# K40_panel_V1.net
KiCad netlist of a schematic drawn in EAGLE
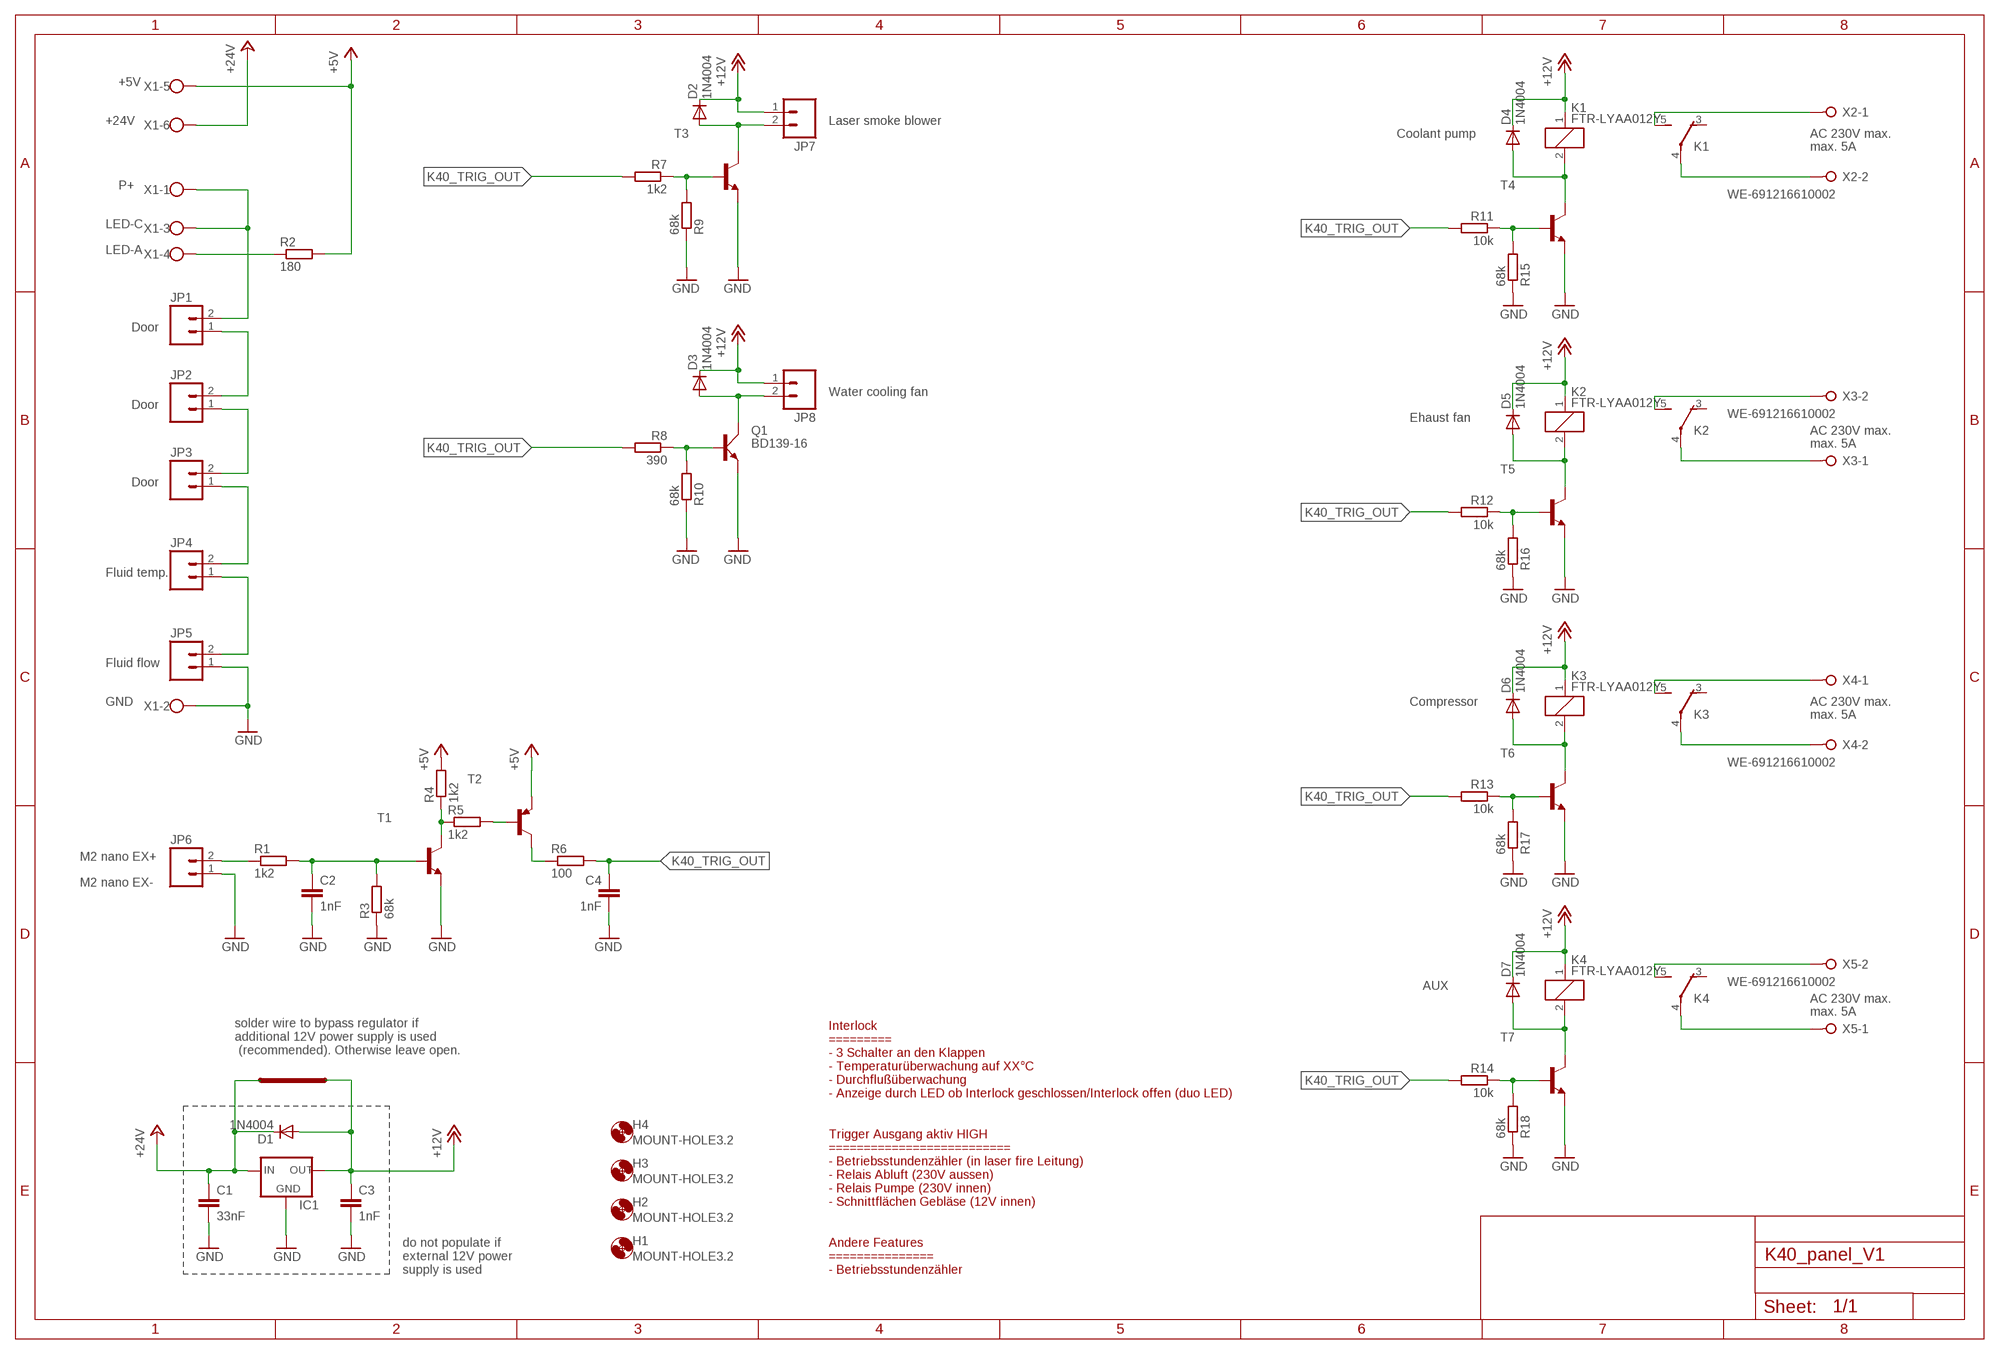
[diagram p0: schematic, sheet 1]

(export (version "E")
  (design (tool "Eeschema 10.0.6"))
  (components
    (comp (ref "C1")
      (value "33nF")
      (footprint "eagle-import:C050-024X044")
      (libsource (lib "eagle-import") (part "C-EU050-024X044"))
    )
    (comp (ref "C2")
      (value "1nF")
      (footprint "eagle-import:C050-024X044")
      (libsource (lib "eagle-import") (part "C-EU050-024X044"))
    )
    (comp (ref "C3")
      (value "1nF")
      (footprint "eagle-import:C050-024X044")
      (libsource (lib "eagle-import") (part "C-EU050-024X044"))
    )
    (comp (ref "C4")
      (value "1nF")
      (footprint "eagle-import:C050-024X044")
      (libsource (lib "eagle-import") (part "C-EU050-024X044"))
    )
    (comp (ref "D1")
      (value "1N4004")
      (footprint "eagle-import:DO41-10")
      (libsource (lib "eagle-import") (part "1N4004"))
    )
    (comp (ref "D2")
      (value "1N4004")
      (footprint "eagle-import:DO41-10")
      (libsource (lib "eagle-import") (part "1N4004"))
    )
    (comp (ref "D3")
      (value "1N4004")
      (footprint "eagle-import:DO41-10")
      (libsource (lib "eagle-import") (part "1N4004"))
    )
    (comp (ref "D4")
      (value "1N4004")
      (footprint "eagle-import:DO41-10")
      (libsource (lib "eagle-import") (part "1N4004"))
    )
    (comp (ref "D5")
      (value "1N4004")
      (footprint "eagle-import:DO41-10")
      (libsource (lib "eagle-import") (part "1N4004"))
    )
    (comp (ref "D6")
      (value "1N4004")
      (footprint "eagle-import:DO41-10")
      (libsource (lib "eagle-import") (part "1N4004"))
    )
    (comp (ref "D7")
      (value "1N4004")
      (footprint "eagle-import:DO41-10")
      (libsource (lib "eagle-import") (part "1N4004"))
    )
    (comp (ref "H1")
      (value "MOUNT-HOLE3.2")
      (footprint "eagle-import:3,2")
      (libsource (lib "eagle-import") (part "MOUNT-HOLE3.2"))
    )
    (comp (ref "H2")
      (value "MOUNT-HOLE3.2")
      (footprint "eagle-import:3,2")
      (libsource (lib "eagle-import") (part "MOUNT-HOLE3.2"))
    )
    (comp (ref "H3")
      (value "MOUNT-HOLE3.2")
      (footprint "eagle-import:3,2")
      (libsource (lib "eagle-import") (part "MOUNT-HOLE3.2"))
    )
    (comp (ref "H4")
      (value "MOUNT-HOLE3.2")
      (footprint "eagle-import:3,2")
      (libsource (lib "eagle-import") (part "MOUNT-HOLE3.2"))
    )
    (comp (ref "IC1")
      (value "78XXS")
      (footprint "eagle-import:78XXS")
      (libsource (lib "eagle-import") (part "78XXS"))
    )
    (comp (ref "JP1")
      (value "M02POLAR")
      (footprint "eagle-import:MOLEX-1X2")
      (libsource (lib "eagle-import") (part "M02POLAR"))
    )
    (comp (ref "JP2")
      (value "M02POLAR")
      (footprint "eagle-import:MOLEX-1X2")
      (libsource (lib "eagle-import") (part "M02POLAR"))
    )
    (comp (ref "JP3")
      (value "M02POLAR")
      (footprint "eagle-import:MOLEX-1X2")
      (libsource (lib "eagle-import") (part "M02POLAR"))
    )
    (comp (ref "JP4")
      (value "M02POLAR")
      (footprint "eagle-import:MOLEX-1X2")
      (libsource (lib "eagle-import") (part "M02POLAR"))
    )
    (comp (ref "JP5")
      (value "M02POLAR")
      (footprint "eagle-import:MOLEX-1X2")
      (libsource (lib "eagle-import") (part "M02POLAR"))
    )
    (comp (ref "JP6")
      (value "M02POLAR")
      (footprint "eagle-import:MOLEX-1X2")
      (libsource (lib "eagle-import") (part "M02POLAR"))
    )
    (comp (ref "JP7")
      (value "M02POLAR")
      (footprint "eagle-import:MOLEX-1X2")
      (libsource (lib "eagle-import") (part "M02POLAR"))
    )
    (comp (ref "JP8")
      (value "M02POLAR")
      (footprint "eagle-import:MOLEX-1X2")
      (libsource (lib "eagle-import") (part "M02POLAR"))
    )
    (comp (ref "K1")
      (value "FTR-LYAA012Y")
      (footprint "eagle-import:FTR-LYC")
      (libsource (lib "eagle-import") (part "FTR-LYC12"))
    )
    (comp (ref "K2")
      (value "FTR-LYAA012Y")
      (footprint "eagle-import:FTR-LYC")
      (libsource (lib "eagle-import") (part "FTR-LYC12"))
    )
    (comp (ref "K3")
      (value "FTR-LYAA012Y")
      (footprint "eagle-import:FTR-LYC")
      (libsource (lib "eagle-import") (part "FTR-LYC12"))
    )
    (comp (ref "K4")
      (value "FTR-LYAA012Y")
      (footprint "eagle-import:FTR-LYC")
      (libsource (lib "eagle-import") (part "FTR-LYC12"))
    )
    (comp (ref "Q1")
      (value "BD139-16")
      (footprint "eagle-import:TO126AV")
      (libsource (lib "eagle-import") (part "BD139"))
    )
    (comp (ref "R1")
      (value "1k2")
      (footprint "eagle-import:0204_7")
      (libsource (lib "eagle-import") (part "R-EU_0204/7"))
    )
    (comp (ref "R2")
      (value "180")
      (footprint "eagle-import:0204_7")
      (libsource (lib "eagle-import") (part "R-EU_0204/7"))
    )
    (comp (ref "R3")
      (value "68k")
      (footprint "eagle-import:0204_7")
      (libsource (lib "eagle-import") (part "R-EU_0204/7"))
    )
    (comp (ref "R4")
      (value "1k2")
      (footprint "eagle-import:0204_7")
      (libsource (lib "eagle-import") (part "R-EU_0204/7"))
    )
    (comp (ref "R5")
      (value "1k2")
      (footprint "eagle-import:0204_7")
      (libsource (lib "eagle-import") (part "R-EU_0204/7"))
    )
    (comp (ref "R6")
      (value "100")
      (footprint "eagle-import:0204_7")
      (libsource (lib "eagle-import") (part "R-EU_0204/7"))
    )
    (comp (ref "R7")
      (value "1k2")
      (footprint "eagle-import:0204_7")
      (libsource (lib "eagle-import") (part "R-EU_0204/7"))
    )
    (comp (ref "R8")
      (value "390")
      (footprint "eagle-import:0204_7")
      (libsource (lib "eagle-import") (part "R-EU_0204/7"))
    )
    (comp (ref "R9")
      (value "68k")
      (footprint "eagle-import:0204_7")
      (libsource (lib "eagle-import") (part "R-EU_0204/7"))
    )
    (comp (ref "R10")
      (value "68k")
      (footprint "eagle-import:0204_7")
      (libsource (lib "eagle-import") (part "R-EU_0204/7"))
    )
    (comp (ref "R11")
      (value "10k")
      (footprint "eagle-import:0204_7")
      (libsource (lib "eagle-import") (part "R-EU_0204/7"))
    )
    (comp (ref "R12")
      (value "10k")
      (footprint "eagle-import:0204_7")
      (libsource (lib "eagle-import") (part "R-EU_0204/7"))
    )
    (comp (ref "R13")
      (value "10k")
      (footprint "eagle-import:0204_7")
      (libsource (lib "eagle-import") (part "R-EU_0204/7"))
    )
    (comp (ref "R14")
      (value "10k")
      (footprint "eagle-import:0204_7")
      (libsource (lib "eagle-import") (part "R-EU_0204/7"))
    )
    (comp (ref "R15")
      (value "68k")
      (footprint "eagle-import:0204_7")
      (libsource (lib "eagle-import") (part "R-EU_0204/7"))
    )
    (comp (ref "R16")
      (value "68k")
      (footprint "eagle-import:0204_7")
      (libsource (lib "eagle-import") (part "R-EU_0204/7"))
    )
    (comp (ref "R17")
      (value "68k")
      (footprint "eagle-import:0204_7")
      (libsource (lib "eagle-import") (part "R-EU_0204/7"))
    )
    (comp (ref "R18")
      (value "68k")
      (footprint "eagle-import:0204_7")
      (libsource (lib "eagle-import") (part "R-EU_0204/7"))
    )
    (comp (ref "T1")
      (value "2N4401-NPN-TO92-EBC")
      (footprint "eagle-import:TO92-EBC")
      (libsource (lib "eagle-import") (part "-NPN-TO92-EBC2N4401"))
    )
    (comp (ref "T2")
      (value "2N4403-PNP-TO92-EBC")
      (footprint "eagle-import:TO92-EBC")
      (libsource (lib "eagle-import") (part "-PNP-TO92-EBC2N4403"))
    )
    (comp (ref "T3")
      (value "2N4401-NPN-TO92-EBC")
      (footprint "eagle-import:TO92-EBC")
      (libsource (lib "eagle-import") (part "-NPN-TO92-EBC2N4401"))
    )
    (comp (ref "T4")
      (value "2N4401-NPN-TO92-EBC")
      (footprint "eagle-import:TO92-EBC")
      (libsource (lib "eagle-import") (part "-NPN-TO92-EBC2N4401"))
    )
    (comp (ref "T5")
      (value "2N4401-NPN-TO92-EBC")
      (footprint "eagle-import:TO92-EBC")
      (libsource (lib "eagle-import") (part "-NPN-TO92-EBC2N4401"))
    )
    (comp (ref "T6")
      (value "2N4401-NPN-TO92-EBC")
      (footprint "eagle-import:TO92-EBC")
      (libsource (lib "eagle-import") (part "-NPN-TO92-EBC2N4401"))
    )
    (comp (ref "T7")
      (value "2N4401-NPN-TO92-EBC")
      (footprint "eagle-import:TO92-EBC")
      (libsource (lib "eagle-import") (part "-NPN-TO92-EBC2N4401"))
    )
    (comp (ref "X1")
      (value "W237-6")
      (footprint "eagle-import:W237-6")
      (libsource (lib "eagle-import") (part "W237-6"))
    )
    (comp (ref "X2")
      (value "WE-691216610002")
      (footprint "eagle-import:W237-2N")
      (libsource (lib "eagle-import") (part "W237-2N"))
    )
    (comp (ref "X3")
      (value "WE-691216610002")
      (footprint "eagle-import:W237-2N")
      (libsource (lib "eagle-import") (part "W237-2N"))
    )
    (comp (ref "X4")
      (value "WE-691216610002")
      (footprint "eagle-import:W237-2N")
      (libsource (lib "eagle-import") (part "W237-2N"))
    )
    (comp (ref "X5")
      (value "WE-691216610002")
      (footprint "eagle-import:W237-2N")
      (libsource (lib "eagle-import") (part "W237-2N"))
    )
  )
  (nets
    (net (code "1") (name "+5V") (class "Default")
      (node (ref "R2") (pin "2") (pinfunction "2_2") (pintype "passive"))
      (node (ref "R4") (pin "2") (pinfunction "2_2") (pintype "passive"))
      (node (ref "T2") (pin "E") (pinfunction "E_E") (pintype "passive"))
      (node (ref "X1") (pin "5") (pinfunction "KL_5") (pintype "passive"))
    )
    (net (code "2") (name "+12V") (class "Default")
      (node (ref "C3") (pin "1") (pinfunction "1_1") (pintype "passive"))
      (node (ref "D1") (pin "A") (pinfunction "A_A") (pintype "passive"))
      (node (ref "D2") (pin "C") (pinfunction "C_C") (pintype "passive"))
      (node (ref "D3") (pin "C") (pinfunction "C_C") (pintype "passive"))
      (node (ref "D4") (pin "C") (pinfunction "C_C") (pintype "passive"))
      (node (ref "D5") (pin "C") (pinfunction "C_C") (pintype "passive"))
      (node (ref "D6") (pin "C") (pinfunction "C_C") (pintype "passive"))
      (node (ref "D7") (pin "C") (pinfunction "C_C") (pintype "passive"))
      (node (ref "IC1") (pin "OUT") (pinfunction "OUT_OUT") (pintype "passive"))
      (node (ref "JP7") (pin "1") (pinfunction "1_1") (pintype "passive"))
      (node (ref "JP8") (pin "1") (pinfunction "1_1") (pintype "passive"))
      (node (ref "K1") (pin "1") (pinfunction "1_1") (pintype "passive"))
      (node (ref "K2") (pin "1") (pinfunction "1_1") (pintype "passive"))
      (node (ref "K3") (pin "1") (pinfunction "1_1") (pintype "passive"))
      (node (ref "K4") (pin "1") (pinfunction "1_1") (pintype "passive"))
    )
    (net (code "3") (name "+24V") (class "Default")
      (node (ref "C1") (pin "1") (pinfunction "1_1") (pintype "passive"))
      (node (ref "D1") (pin "C") (pinfunction "C_C") (pintype "passive"))
      (node (ref "IC1") (pin "IN") (pinfunction "IN_IN") (pintype "input"))
      (node (ref "X1") (pin "6") (pinfunction "KL_6") (pintype "passive"))
    )
    (net (code "4") (name "GND") (class "Default")
      (node (ref "C1") (pin "2") (pinfunction "2_2") (pintype "passive"))
      (node (ref "C2") (pin "2") (pinfunction "2_2") (pintype "passive"))
      (node (ref "C3") (pin "2") (pinfunction "2_2") (pintype "passive"))
      (node (ref "C4") (pin "2") (pinfunction "2_2") (pintype "passive"))
      (node (ref "IC1") (pin "GND") (pinfunction "GND_GND") (pintype "input"))
      (node (ref "JP5") (pin "1") (pinfunction "1_1") (pintype "passive"))
      (node (ref "JP6") (pin "1") (pinfunction "1_1") (pintype "passive"))
      (node (ref "Q1") (pin "E") (pinfunction "E_E") (pintype "passive"))
      (node (ref "R10") (pin "1") (pinfunction "1_1") (pintype "passive"))
      (node (ref "R15") (pin "1") (pinfunction "1_1") (pintype "passive"))
      (node (ref "R16") (pin "1") (pinfunction "1_1") (pintype "passive"))
      (node (ref "R17") (pin "1") (pinfunction "1_1") (pintype "passive"))
      (node (ref "R18") (pin "1") (pinfunction "1_1") (pintype "passive"))
      (node (ref "R3") (pin "1") (pinfunction "1_1") (pintype "passive"))
      (node (ref "R9") (pin "1") (pinfunction "1_1") (pintype "passive"))
      (node (ref "T1") (pin "E") (pinfunction "E_E") (pintype "passive"))
      (node (ref "T3") (pin "E") (pinfunction "E_E") (pintype "passive"))
      (node (ref "T4") (pin "E") (pinfunction "E_E") (pintype "passive"))
      (node (ref "T5") (pin "E") (pinfunction "E_E") (pintype "passive"))
      (node (ref "T6") (pin "E") (pinfunction "E_E") (pintype "passive"))
      (node (ref "T7") (pin "E") (pinfunction "E_E") (pintype "passive"))
      (node (ref "X1") (pin "2") (pinfunction "KL_2") (pintype "passive"))
    )
    (net (code "5") (name "K40_TRIG_OUT") (class "Default")
      (node (ref "C4") (pin "1") (pinfunction "1_1") (pintype "passive"))
      (node (ref "R11") (pin "2") (pinfunction "2_2") (pintype "passive"))
      (node (ref "R12") (pin "2") (pinfunction "2_2") (pintype "passive"))
      (node (ref "R13") (pin "2") (pinfunction "2_2") (pintype "passive"))
      (node (ref "R14") (pin "2") (pinfunction "2_2") (pintype "passive"))
      (node (ref "R6") (pin "2") (pinfunction "2_2") (pintype "passive"))
      (node (ref "R7") (pin "2") (pinfunction "2_2") (pintype "passive"))
      (node (ref "R8") (pin "2") (pinfunction "2_2") (pintype "passive"))
    )
    (net (code "6") (name "Net-(C2-Pad1)") (class "Default")
      (node (ref "C2") (pin "1") (pinfunction "1_1") (pintype "passive"))
      (node (ref "R1") (pin "2") (pinfunction "2_2") (pintype "passive"))
      (node (ref "R3") (pin "2") (pinfunction "2_2") (pintype "passive"))
      (node (ref "T1") (pin "B") (pinfunction "B_B") (pintype "passive"))
    )
    (net (code "7") (name "Net-(D2-PadA)") (class "Default")
      (node (ref "D2") (pin "A") (pinfunction "A_A") (pintype "passive"))
      (node (ref "JP7") (pin "2") (pinfunction "2_2") (pintype "passive"))
      (node (ref "T3") (pin "C") (pinfunction "C_C") (pintype "passive"))
    )
    (net (code "8") (name "Net-(D3-PadA)") (class "Default")
      (node (ref "D3") (pin "A") (pinfunction "A_A") (pintype "passive"))
      (node (ref "JP8") (pin "2") (pinfunction "2_2") (pintype "passive"))
      (node (ref "Q1") (pin "C") (pinfunction "C_C") (pintype "passive"))
    )
    (net (code "9") (name "Net-(D4-PadA)") (class "Default")
      (node (ref "D4") (pin "A") (pinfunction "A_A") (pintype "passive"))
      (node (ref "K1") (pin "2") (pinfunction "2_2") (pintype "passive"))
      (node (ref "T4") (pin "C") (pinfunction "C_C") (pintype "passive"))
    )
    (net (code "10") (name "Net-(D5-PadA)") (class "Default")
      (node (ref "D5") (pin "A") (pinfunction "A_A") (pintype "passive"))
      (node (ref "K2") (pin "2") (pinfunction "2_2") (pintype "passive"))
      (node (ref "T5") (pin "C") (pinfunction "C_C") (pintype "passive"))
    )
    (net (code "11") (name "Net-(D6-PadA)") (class "Default")
      (node (ref "D6") (pin "A") (pinfunction "A_A") (pintype "passive"))
      (node (ref "K3") (pin "2") (pinfunction "2_2") (pintype "passive"))
      (node (ref "T6") (pin "C") (pinfunction "C_C") (pintype "passive"))
    )
    (net (code "12") (name "Net-(D7-PadA)") (class "Default")
      (node (ref "D7") (pin "A") (pinfunction "A_A") (pintype "passive"))
      (node (ref "K4") (pin "2") (pinfunction "2_2") (pintype "passive"))
      (node (ref "T7") (pin "C") (pinfunction "C_C") (pintype "passive"))
    )
    (net (code "13") (name "Net-(JP1-Pad1)") (class "Default")
      (node (ref "JP1") (pin "1") (pinfunction "1_1") (pintype "passive"))
      (node (ref "JP2") (pin "2") (pinfunction "2_2") (pintype "passive"))
    )
    (net (code "14") (name "Net-(JP2-Pad1)") (class "Default")
      (node (ref "JP2") (pin "1") (pinfunction "1_1") (pintype "passive"))
      (node (ref "JP3") (pin "2") (pinfunction "2_2") (pintype "passive"))
    )
    (net (code "15") (name "Net-(JP3-Pad1)") (class "Default")
      (node (ref "JP3") (pin "1") (pinfunction "1_1") (pintype "passive"))
      (node (ref "JP4") (pin "2") (pinfunction "2_2") (pintype "passive"))
    )
    (net (code "16") (name "Net-(JP4-Pad1)") (class "Default")
      (node (ref "JP4") (pin "1") (pinfunction "1_1") (pintype "passive"))
      (node (ref "JP5") (pin "2") (pinfunction "2_2") (pintype "passive"))
    )
    (net (code "17") (name "Net-(JP6-Pad2)") (class "Default")
      (node (ref "JP6") (pin "2") (pinfunction "2_2") (pintype "passive"))
      (node (ref "R1") (pin "1") (pinfunction "1_1") (pintype "passive"))
    )
    (net (code "18") (name "Net-(K1A-P)") (class "Default")
      (node (ref "K1") (pin "4") (pinfunction "P_4") (pintype "passive"))
      (node (ref "X2") (pin "2") (pinfunction "KL_2") (pintype "passive"))
    )
    (net (code "19") (name "Net-(K1A-S)") (class "Default")
      (node (ref "K1") (pin "5") (pinfunction "S_5") (pintype "passive"))
      (node (ref "X2") (pin "1") (pinfunction "KL_1") (pintype "passive"))
    )
    (net (code "20") (name "Net-(K2A-P)") (class "Default")
      (node (ref "K2") (pin "4") (pinfunction "P_4") (pintype "passive"))
      (node (ref "X3") (pin "1") (pinfunction "KL_1") (pintype "passive"))
    )
    (net (code "21") (name "Net-(K2A-S)") (class "Default")
      (node (ref "K2") (pin "5") (pinfunction "S_5") (pintype "passive"))
      (node (ref "X3") (pin "2") (pinfunction "KL_2") (pintype "passive"))
    )
    (net (code "22") (name "Net-(K3A-P)") (class "Default")
      (node (ref "K3") (pin "4") (pinfunction "P_4") (pintype "passive"))
      (node (ref "X4") (pin "2") (pinfunction "KL_2") (pintype "passive"))
    )
    (net (code "23") (name "Net-(K3A-S)") (class "Default")
      (node (ref "K3") (pin "5") (pinfunction "S_5") (pintype "passive"))
      (node (ref "X4") (pin "1") (pinfunction "KL_1") (pintype "passive"))
    )
    (net (code "24") (name "Net-(K4A-P)") (class "Default")
      (node (ref "K4") (pin "4") (pinfunction "P_4") (pintype "passive"))
      (node (ref "X5") (pin "1") (pinfunction "KL_1") (pintype "passive"))
    )
    (net (code "25") (name "Net-(K4A-S)") (class "Default")
      (node (ref "K4") (pin "5") (pinfunction "S_5") (pintype "passive"))
      (node (ref "X5") (pin "2") (pinfunction "KL_2") (pintype "passive"))
    )
    (net (code "26") (name "Net-(Q1-PadB)") (class "Default")
      (node (ref "Q1") (pin "B") (pinfunction "B_B") (pintype "passive"))
      (node (ref "R10") (pin "2") (pinfunction "2_2") (pintype "passive"))
      (node (ref "R8") (pin "1") (pinfunction "1_1") (pintype "passive"))
    )
    (net (code "27") (name "Net-(R4-Pad1)") (class "Default")
      (node (ref "R4") (pin "1") (pinfunction "1_1") (pintype "passive"))
      (node (ref "R5") (pin "1") (pinfunction "1_1") (pintype "passive"))
      (node (ref "T1") (pin "C") (pinfunction "C_C") (pintype "passive"))
    )
    (net (code "28") (name "Net-(R5-Pad2)") (class "Default")
      (node (ref "R5") (pin "2") (pinfunction "2_2") (pintype "passive"))
      (node (ref "T2") (pin "B") (pinfunction "B_B") (pintype "passive"))
    )
    (net (code "29") (name "Net-(R6-Pad1)") (class "Default")
      (node (ref "R6") (pin "1") (pinfunction "1_1") (pintype "passive"))
      (node (ref "T2") (pin "C") (pinfunction "C_C") (pintype "passive"))
    )
    (net (code "30") (name "Net-(R7-Pad1)") (class "Default")
      (node (ref "R7") (pin "1") (pinfunction "1_1") (pintype "passive"))
      (node (ref "R9") (pin "2") (pinfunction "2_2") (pintype "passive"))
      (node (ref "T3") (pin "B") (pinfunction "B_B") (pintype "passive"))
    )
    (net (code "31") (name "Net-(R11-Pad1)") (class "Default")
      (node (ref "R11") (pin "1") (pinfunction "1_1") (pintype "passive"))
      (node (ref "R15") (pin "2") (pinfunction "2_2") (pintype "passive"))
      (node (ref "T4") (pin "B") (pinfunction "B_B") (pintype "passive"))
    )
    (net (code "32") (name "Net-(R12-Pad1)") (class "Default")
      (node (ref "R12") (pin "1") (pinfunction "1_1") (pintype "passive"))
      (node (ref "R16") (pin "2") (pinfunction "2_2") (pintype "passive"))
      (node (ref "T5") (pin "B") (pinfunction "B_B") (pintype "passive"))
    )
    (net (code "33") (name "Net-(R13-Pad1)") (class "Default")
      (node (ref "R13") (pin "1") (pinfunction "1_1") (pintype "passive"))
      (node (ref "R17") (pin "2") (pinfunction "2_2") (pintype "passive"))
      (node (ref "T6") (pin "B") (pinfunction "B_B") (pintype "passive"))
    )
    (net (code "34") (name "Net-(R14-Pad1)") (class "Default")
      (node (ref "R14") (pin "1") (pinfunction "1_1") (pintype "passive"))
      (node (ref "R18") (pin "2") (pinfunction "2_2") (pintype "passive"))
      (node (ref "T7") (pin "B") (pinfunction "B_B") (pintype "passive"))
    )
    (net (code "35") (name "Net-(X1A-KL)") (class "Default")
      (node (ref "JP1") (pin "2") (pinfunction "2_2") (pintype "passive"))
      (node (ref "X1") (pin "1") (pinfunction "KL_1") (pintype "passive"))
      (node (ref "X1") (pin "3") (pinfunction "KL_3") (pintype "passive"))
    )
    (net (code "36") (name "Net-(X1D-KL)") (class "Default")
      (node (ref "R2") (pin "1") (pinfunction "1_1") (pintype "passive"))
      (node (ref "X1") (pin "4") (pinfunction "KL_4") (pintype "passive"))
    )
    (net (code "37") (name "unconnected-(K1A-O-Pad3)") (class "Default")
      (node (ref "K1") (pin "3") (pinfunction "O_3") (pintype "passive"))
    )
    (net (code "38") (name "unconnected-(K2A-O-Pad3)") (class "Default")
      (node (ref "K2") (pin "3") (pinfunction "O_3") (pintype "passive"))
    )
    (net (code "39") (name "unconnected-(K3A-O-Pad3)") (class "Default")
      (node (ref "K3") (pin "3") (pinfunction "O_3") (pintype "passive"))
    )
    (net (code "40") (name "unconnected-(K4A-O-Pad3)") (class "Default")
      (node (ref "K4") (pin "3") (pinfunction "O_3") (pintype "passive"))
    )
  )
)
